# dac.net
KiCad netlist of a schematic drawn in Altium Designer
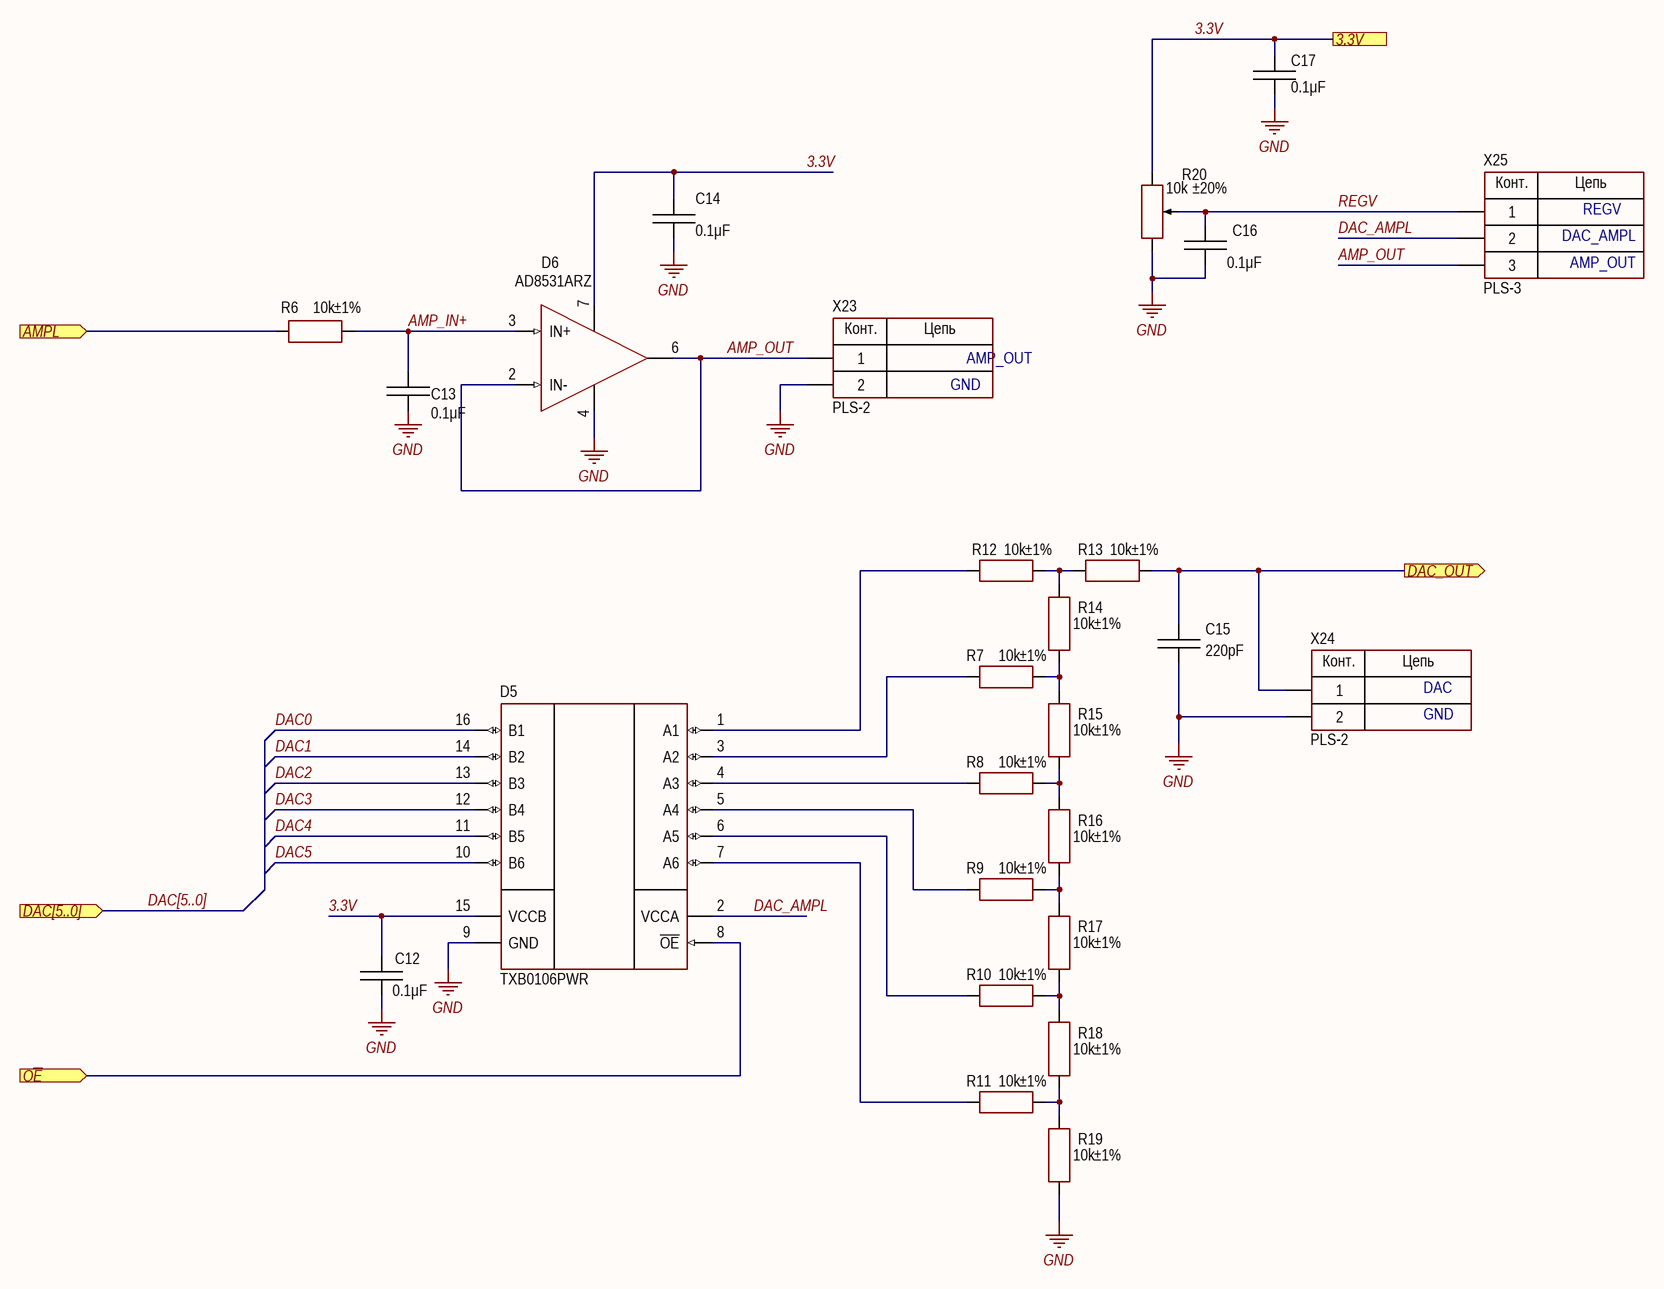
[diagram p0: dac.SchDoc]

(export (version "E")
  (design (tool "Eeschema 10.0.6"))
  (components
    (comp (ref "C12")
      (value "0.1μF")
      (footprint "CAP: 1206")
      (fields
        (field (name "MANUFACTURER") "Murata Electronics")
        (field (name "PARTNUMBER") "GRM319R71H104K")
        (field (name "VALUEMANUFACTURERPARTNUMBER") "Ceramic capacitor, 0.1μF, X7R, ±10%, 50V, 1206, -55...+125°C")
      )
      (libsource (lib "capacitor") (part "Ceramic_1206"))
    )
    (comp (ref "C13")
      (value "0.1μF")
      (footprint "CAP: 1206")
      (fields
        (field (name "MANUFACTURER") "Murata Electronics")
        (field (name "PARTNUMBER") "GRM319R71H104K")
        (field (name "VALUEMANUFACTURERPARTNUMBER") "Ceramic capacitor, 0.1μF, X7R, ±10%, 50V, 1206, -55...+125°C")
      )
      (libsource (lib "capacitor") (part "Ceramic_1206"))
    )
    (comp (ref "C14")
      (value "0.1μF")
      (footprint "CAP: 1206")
      (fields
        (field (name "MANUFACTURER") "Murata Electronics")
        (field (name "PARTNUMBER") "GRM319R71H104K")
        (field (name "VALUEMANUFACTURERPARTNUMBER") "Ceramic capacitor, 0.1μF, X7R, ±10%, 50V, 1206, -55...+125°C")
      )
      (libsource (lib "capacitor") (part "Ceramic_1206"))
    )
    (comp (ref "C15")
      (value "220pF")
      (footprint "CAP: 1206")
      (fields
        (field (name "MANUFACTURER") "Yageo")
        (field (name "PARTNUMBER") "CC1206KRX7R9BB104")
        (field (name "VALUEMANUFACTURERPARTNUMBER") "Ceramic capacitor, 220pF, X7R, ±10%, 50V, 1206, -55...+125°C")
      )
      (libsource (lib "capacitor") (part "Ceramic_1206"))
    )
    (comp (ref "C16")
      (value "0.1μF")
      (footprint "CAP: 1206")
      (fields
        (field (name "MANUFACTURER") "Murata Electronics")
        (field (name "PARTNUMBER") "GRM319R71H104K")
        (field (name "VALUEMANUFACTURERPARTNUMBER") "Ceramic capacitor, 0.1μF, X7R, ±10%, 50V, 1206, -55...+125°C")
      )
      (libsource (lib "capacitor") (part "Ceramic_1206"))
    )
    (comp (ref "C17")
      (value "0.1μF")
      (footprint "CAP: 1206")
      (fields
        (field (name "MANUFACTURER") "Murata Electronics")
        (field (name "PARTNUMBER") "GRM319R71H104K")
        (field (name "VALUEMANUFACTURERPARTNUMBER") "Ceramic capacitor, 0.1μF, X7R, ±10%, 50V, 1206, -55...+125°C")
      )
      (libsource (lib "capacitor") (part "Ceramic_1206"))
    )
    (comp (ref "D5")
      (value "~")
      (footprint "16-TSSOP")
      (description "6-Bit Bidirectional Level-Shifting and Voltage Translator")
      (fields (field (name "MANUFACTURER") "Texas Instruments") (field (name "PARTNUMBER") "TXB0106PWR"))
      (libsource (lib "ic-logic") (part "TXB0106PWR"))
    )
    (comp (ref "D6")
      (value "~")
      (footprint "8-SOIC")
      (description "OP amplifier Rail-to-Rail 3MHz")
      (fields
        (field (name "MANUFACTURER") "Analog Devices Inc.")
        (field (name "VALUEMANUFACTURERPARTNUMBER") "IC op amplifier, Rail-to-Rail, 3MHz, 2.7V ~ 6V, ±1.35V ~3V, -40°C ~ 85°C, 8-SOIC")
        (field (name "PARTNUMBER") "AD8531ARZ")
      )
      (libsource (lib "ic-amplifier") (part "AD8531ARZ"))
    )
    (comp (ref "R6")
      (value "10k")
      (footprint "RES: 1206")
      (fields
        (field (name "MANUFACTURER") "Yageo")
        (field (name "PARTNUMBER") "RC1206JR-07100RL")
        (field (name "VALUEMANUFACTURERPARTNUMBER") "Resistor film, 10k, ±1%, 1206, 0.25W, -55...+125°C")
        (field (name "TOLERANCE") "±1%")
      )
      (libsource (lib "") (part "Resistor_1206_1"))
    )
    (comp (ref "R7")
      (value "10k")
      (footprint "RES: 1206")
      (fields
        (field (name "MANUFACTURER") "Yageo")
        (field (name "PARTNUMBER") "RC1206JR-07100RL")
        (field (name "VALUEMANUFACTURERPARTNUMBER") "Resistor film, 10k, ±1%, 1206, 0.25W, -55...+125°C")
        (field (name "TOLERANCE") "±1%")
      )
      (libsource (lib "") (part "Resistor_1206_1"))
    )
    (comp (ref "R8")
      (value "10k")
      (footprint "RES: 1206")
      (fields
        (field (name "MANUFACTURER") "Yageo")
        (field (name "PARTNUMBER") "RC1206JR-07100RL")
        (field (name "VALUEMANUFACTURERPARTNUMBER") "Resistor film, 10k, ±1%, 1206, 0.25W, -55...+125°C")
        (field (name "TOLERANCE") "±1%")
      )
      (libsource (lib "") (part "Resistor_1206_1"))
    )
    (comp (ref "R9")
      (value "10k")
      (footprint "RES: 1206")
      (fields
        (field (name "MANUFACTURER") "Yageo")
        (field (name "PARTNUMBER") "RC1206JR-07100RL")
        (field (name "VALUEMANUFACTURERPARTNUMBER") "Resistor film, 10k, ±1%, 1206, 0.25W, -55...+125°C")
        (field (name "TOLERANCE") "±1%")
      )
      (libsource (lib "") (part "Resistor_1206_1"))
    )
    (comp (ref "R10")
      (value "10k")
      (footprint "RES: 1206")
      (fields
        (field (name "MANUFACTURER") "Yageo")
        (field (name "PARTNUMBER") "RC1206JR-07100RL")
        (field (name "VALUEMANUFACTURERPARTNUMBER") "Resistor film, 10k, ±1%, 1206, 0.25W, -55...+125°C")
        (field (name "TOLERANCE") "±1%")
      )
      (libsource (lib "") (part "Resistor_1206_1"))
    )
    (comp (ref "R11")
      (value "10k")
      (footprint "RES: 1206")
      (fields
        (field (name "MANUFACTURER") "Yageo")
        (field (name "PARTNUMBER") "RC1206JR-07100RL")
        (field (name "VALUEMANUFACTURERPARTNUMBER") "Resistor film, 10k, ±1%, 1206, 0.25W, -55...+125°C")
        (field (name "TOLERANCE") "±1%")
      )
      (libsource (lib "") (part "Resistor_1206_1"))
    )
    (comp (ref "R12")
      (value "10k")
      (footprint "RES: 1206")
      (fields
        (field (name "MANUFACTURER") "Yageo")
        (field (name "PARTNUMBER") "RC1206JR-07100RL")
        (field (name "VALUEMANUFACTURERPARTNUMBER") "Resistor film, 10k, ±1%, 1206, 0.25W, -55...+125°C")
        (field (name "TOLERANCE") "±1%")
      )
      (libsource (lib "") (part "Resistor_1206_1"))
    )
    (comp (ref "R13")
      (value "10k")
      (footprint "RES: 1206")
      (fields
        (field (name "MANUFACTURER") "Yageo")
        (field (name "PARTNUMBER") "RC1206JR-07100RL")
        (field (name "VALUEMANUFACTURERPARTNUMBER") "Resistor film, 10k, ±1%, 1206, 0.25W, -55...+125°C")
        (field (name "TOLERANCE") "±1%")
      )
      (libsource (lib "") (part "Resistor_1206_1"))
    )
    (comp (ref "R14")
      (value "10k")
      (footprint "RES: 1206")
      (fields
        (field (name "MANUFACTURER") "Yageo")
        (field (name "PARTNUMBER") "RC1206JR-07100RL")
        (field (name "VALUEMANUFACTURERPARTNUMBER") "Resistor film, 10k, ±1%, 1206, 0.25W, -55...+125°C")
        (field (name "TOLERANCE") "±1%")
      )
      (libsource (lib "resistor") (part "Resistor_1206"))
    )
    (comp (ref "R15")
      (value "10k")
      (footprint "RES: 1206")
      (fields
        (field (name "MANUFACTURER") "Yageo")
        (field (name "PARTNUMBER") "RC1206JR-07100RL")
        (field (name "VALUEMANUFACTURERPARTNUMBER") "Resistor film, 10k, ±1%, 1206, 0.25W, -55...+125°C")
        (field (name "TOLERANCE") "±1%")
      )
      (libsource (lib "resistor") (part "Resistor_1206"))
    )
    (comp (ref "R16")
      (value "10k")
      (footprint "RES: 1206")
      (fields
        (field (name "MANUFACTURER") "Yageo")
        (field (name "PARTNUMBER") "RC1206JR-07100RL")
        (field (name "VALUEMANUFACTURERPARTNUMBER") "Resistor film, 10k, ±1%, 1206, 0.25W, -55...+125°C")
        (field (name "TOLERANCE") "±1%")
      )
      (libsource (lib "resistor") (part "Resistor_1206"))
    )
    (comp (ref "R17")
      (value "10k")
      (footprint "RES: 1206")
      (fields
        (field (name "MANUFACTURER") "Yageo")
        (field (name "PARTNUMBER") "RC1206JR-07100RL")
        (field (name "VALUEMANUFACTURERPARTNUMBER") "Resistor film, 10k, ±1%, 1206, 0.25W, -55...+125°C")
        (field (name "TOLERANCE") "±1%")
      )
      (libsource (lib "resistor") (part "Resistor_1206"))
    )
    (comp (ref "R18")
      (value "10k")
      (footprint "RES: 1206")
      (fields
        (field (name "MANUFACTURER") "Yageo")
        (field (name "PARTNUMBER") "RC1206JR-07100RL")
        (field (name "VALUEMANUFACTURERPARTNUMBER") "Resistor film, 10k, ±1%, 1206, 0.25W, -55...+125°C")
        (field (name "TOLERANCE") "±1%")
      )
      (libsource (lib "resistor") (part "Resistor_1206"))
    )
    (comp (ref "R19")
      (value "10k")
      (footprint "RES: 1206")
      (fields
        (field (name "MANUFACTURER") "Yageo")
        (field (name "PARTNUMBER") "RC1206JR-07100RL")
        (field (name "VALUEMANUFACTURERPARTNUMBER") "Resistor film, 10k, ±1%, 1206, 0.25W, -55...+125°C")
        (field (name "TOLERANCE") "±1%")
      )
      (libsource (lib "resistor") (part "Resistor_1206"))
    )
    (comp (ref "R20")
      (value "10k")
      (footprint "RES: 3314G")
      (fields
        (field (name "MANUFACTURER") "Bourns")
        (field (name "PARTNUMBER") "3314G-1-103E")
        (field (name "VALUEMANUFACTURERPARTNUMBER") ", 10k, ±20%, 3314G, 0.25W, -55...+125°C")
        (field (name "TOLERANCE") "±20%")
      )
      (libsource (lib "resistor") (part "Trimmer"))
    )
    (comp (ref "X23")
      (value "~")
      (footprint "CON: PLS-2")
      (fields
        (field (name "MANUFACTURER") "Connfly")
        (field (name "VALUEMANUFACTURERPARTNUMBER") "Connector, 2pin, 2.54mm, 500VAC, 3A")
        (field (name "PARTNUMBER") "PLS-2")
        (field (name "COMMENTTEXT") "PLS-2")
      )
      (libsource (lib "connector") (part "PLS-2"))
    )
    (comp (ref "X24")
      (value "~")
      (footprint "CON: PLS-2")
      (fields
        (field (name "MANUFACTURER") "Connfly")
        (field (name "VALUEMANUFACTURERPARTNUMBER") "Connector, 2pin, 2.54mm, 500VAC, 3A")
        (field (name "PARTNUMBER") "PLS-2")
        (field (name "COMMENTTEXT") "PLS-2")
      )
      (libsource (lib "connector") (part "PLS-2"))
    )
    (comp (ref "X25")
      (value "~")
      (footprint "CON: PLS-3")
      (fields
        (field (name "MANUFACTURER") "Connfly")
        (field (name "VALUEMANUFACTURERPARTNUMBER") "Connector, 3pin, 2.54mm, 500VAC, 3A")
        (field (name "PARTNUMBER") "PLS-3")
        (field (name "COMMENTTEXT") "PLS-3")
      )
      (libsource (lib "connector") (part "PLS-3"))
    )
  )
  (nets
    (net (code "1") (name "/3.3V") (class "Default")
      (node (ref "C12") (pin "2") (pinfunction "2_2") (pintype "passive"))
      (node (ref "C14") (pin "2") (pinfunction "2_2") (pintype "passive"))
      (node (ref "C17") (pin "2") (pinfunction "2_2") (pintype "passive"))
      (node (ref "D5") (pin "15") (pinfunction "VCCB_15") (pintype "passive"))
      (node (ref "D6") (pin "7") (pinfunction "V+_7") (pintype "power_in"))
      (node (ref "R20") (pin "1") (pinfunction "1_1") (pintype "passive"))
    )
    (net (code "2") (name "/AMPL") (class "Default")
      (node (ref "R6") (pin "2") (pinfunction "2_2") (pintype "passive"))
    )
    (net (code "3") (name "/AMP_IN+") (class "Default")
      (node (ref "C13") (pin "2") (pinfunction "2_2") (pintype "passive"))
      (node (ref "D6") (pin "3") (pinfunction "IN+_3") (pintype "input"))
      (node (ref "R6") (pin "1") (pinfunction "1_1") (pintype "passive"))
    )
    (net (code "4") (name "/AMP_OUT") (class "Default")
      (node (ref "D6") (pin "2") (pinfunction "IN-_2") (pintype "input"))
      (node (ref "D6") (pin "6") (pinfunction "OUT_6") (pintype "passive"))
      (node (ref "X23") (pin "1") (pinfunction "1_1") (pintype "passive"))
      (node (ref "X25") (pin "3") (pinfunction "3_3") (pintype "passive"))
    )
    (net (code "5") (name "/DAC0") (class "Default")
      (node (ref "D5") (pin "16") (pinfunction "B1_16") (pintype "bidirectional"))
    )
    (net (code "6") (name "/DAC1") (class "Default")
      (node (ref "D5") (pin "14") (pinfunction "B2_14") (pintype "bidirectional"))
    )
    (net (code "7") (name "/DAC2") (class "Default")
      (node (ref "D5") (pin "13") (pinfunction "B3_13") (pintype "bidirectional"))
    )
    (net (code "8") (name "/DAC3") (class "Default")
      (node (ref "D5") (pin "12") (pinfunction "B4_12") (pintype "bidirectional"))
    )
    (net (code "9") (name "/DAC4") (class "Default")
      (node (ref "D5") (pin "11") (pinfunction "B5_11") (pintype "bidirectional"))
    )
    (net (code "10") (name "/DAC5") (class "Default")
      (node (ref "D5") (pin "10") (pinfunction "B6_10") (pintype "bidirectional"))
    )
    (net (code "12") (name "/DAC_AMPL") (class "Default")
      (node (ref "D5") (pin "2") (pinfunction "VCCA_2") (pintype "passive"))
      (node (ref "X25") (pin "2") (pinfunction "2_2") (pintype "passive"))
    )
    (net (code "13") (name "/DAC_OUT") (class "Default")
      (node (ref "C15") (pin "2") (pinfunction "2_2") (pintype "passive"))
      (node (ref "R13") (pin "1") (pinfunction "1_1") (pintype "passive"))
      (node (ref "X24") (pin "1") (pinfunction "1_1") (pintype "passive"))
    )
    (net (code "14") (name "/O~{E}") (class "Default")
      (node (ref "D5") (pin "8") (pinfunction "~{OE}_8") (pintype "input"))
    )
    (net (code "15") (name "/REGV") (class "Default")
      (node (ref "C16") (pin "2") (pinfunction "2_2") (pintype "passive"))
      (node (ref "R20") (pin "2") (pinfunction "2_2") (pintype "passive"))
      (node (ref "X25") (pin "1") (pinfunction "1_1") (pintype "passive"))
    )
    (net (code "16") (name "GND") (class "Default")
      (node (ref "C12") (pin "1") (pinfunction "1_1") (pintype "passive"))
      (node (ref "C13") (pin "1") (pinfunction "1_1") (pintype "passive"))
      (node (ref "C14") (pin "1") (pinfunction "1_1") (pintype "passive"))
      (node (ref "C15") (pin "1") (pinfunction "1_1") (pintype "passive"))
      (node (ref "C16") (pin "1") (pinfunction "1_1") (pintype "passive"))
      (node (ref "C17") (pin "1") (pinfunction "1_1") (pintype "passive"))
      (node (ref "D5") (pin "9") (pinfunction "GND_9") (pintype "passive"))
      (node (ref "D6") (pin "4") (pinfunction "V-_4") (pintype "power_in"))
      (node (ref "R19") (pin "2") (pinfunction "2_2") (pintype "passive"))
      (node (ref "R20") (pin "3") (pinfunction "3_3") (pintype "passive"))
      (node (ref "X23") (pin "2") (pinfunction "2_2") (pintype "passive"))
      (node (ref "X24") (pin "2") (pinfunction "2_2") (pintype "passive"))
    )
    (net (code "17") (name "Net-(D5-A1)") (class "Default")
      (node (ref "D5") (pin "1") (pinfunction "A1_1") (pintype "bidirectional"))
      (node (ref "R12") (pin "2") (pinfunction "2_2") (pintype "passive"))
    )
    (net (code "18") (name "Net-(D5-A2)") (class "Default")
      (node (ref "D5") (pin "3") (pinfunction "A2_3") (pintype "bidirectional"))
      (node (ref "R7") (pin "2") (pinfunction "2_2") (pintype "passive"))
    )
    (net (code "19") (name "Net-(D5-A3)") (class "Default")
      (node (ref "D5") (pin "4") (pinfunction "A3_4") (pintype "bidirectional"))
      (node (ref "R8") (pin "2") (pinfunction "2_2") (pintype "passive"))
    )
    (net (code "20") (name "Net-(D5-A4)") (class "Default")
      (node (ref "D5") (pin "5") (pinfunction "A4_5") (pintype "bidirectional"))
      (node (ref "R9") (pin "2") (pinfunction "2_2") (pintype "passive"))
    )
    (net (code "21") (name "Net-(D5-A5)") (class "Default")
      (node (ref "D5") (pin "6") (pinfunction "A5_6") (pintype "bidirectional"))
      (node (ref "R10") (pin "2") (pinfunction "2_2") (pintype "passive"))
    )
    (net (code "22") (name "Net-(D5-A6)") (class "Default")
      (node (ref "D5") (pin "7") (pinfunction "A6_7") (pintype "bidirectional"))
      (node (ref "R11") (pin "2") (pinfunction "2_2") (pintype "passive"))
    )
    (net (code "23") (name "Net-(R10-Pad1)") (class "Default")
      (node (ref "R10") (pin "1") (pinfunction "1_1") (pintype "passive"))
      (node (ref "R17") (pin "2") (pinfunction "2_2") (pintype "passive"))
      (node (ref "R18") (pin "1") (pinfunction "1_1") (pintype "passive"))
    )
    (net (code "24") (name "Net-(R11-Pad1)") (class "Default")
      (node (ref "R11") (pin "1") (pinfunction "1_1") (pintype "passive"))
      (node (ref "R18") (pin "2") (pinfunction "2_2") (pintype "passive"))
      (node (ref "R19") (pin "1") (pinfunction "1_1") (pintype "passive"))
    )
    (net (code "25") (name "Net-(R12-Pad1)") (class "Default")
      (node (ref "R12") (pin "1") (pinfunction "1_1") (pintype "passive"))
      (node (ref "R13") (pin "2") (pinfunction "2_2") (pintype "passive"))
      (node (ref "R14") (pin "1") (pinfunction "1_1") (pintype "passive"))
    )
    (net (code "26") (name "Net-(R14-Pad2)") (class "Default")
      (node (ref "R14") (pin "2") (pinfunction "2_2") (pintype "passive"))
      (node (ref "R15") (pin "1") (pinfunction "1_1") (pintype "passive"))
      (node (ref "R7") (pin "1") (pinfunction "1_1") (pintype "passive"))
    )
    (net (code "27") (name "Net-(R15-Pad2)") (class "Default")
      (node (ref "R15") (pin "2") (pinfunction "2_2") (pintype "passive"))
      (node (ref "R16") (pin "1") (pinfunction "1_1") (pintype "passive"))
      (node (ref "R8") (pin "1") (pinfunction "1_1") (pintype "passive"))
    )
    (net (code "28") (name "Net-(R16-Pad2)") (class "Default")
      (node (ref "R16") (pin "2") (pinfunction "2_2") (pintype "passive"))
      (node (ref "R17") (pin "1") (pinfunction "1_1") (pintype "passive"))
      (node (ref "R9") (pin "1") (pinfunction "1_1") (pintype "passive"))
    )
  )
)
